# A1_0-_-1_0-_220V_12V.net
KiCad netlist of a schematic drawn in Altium Designer
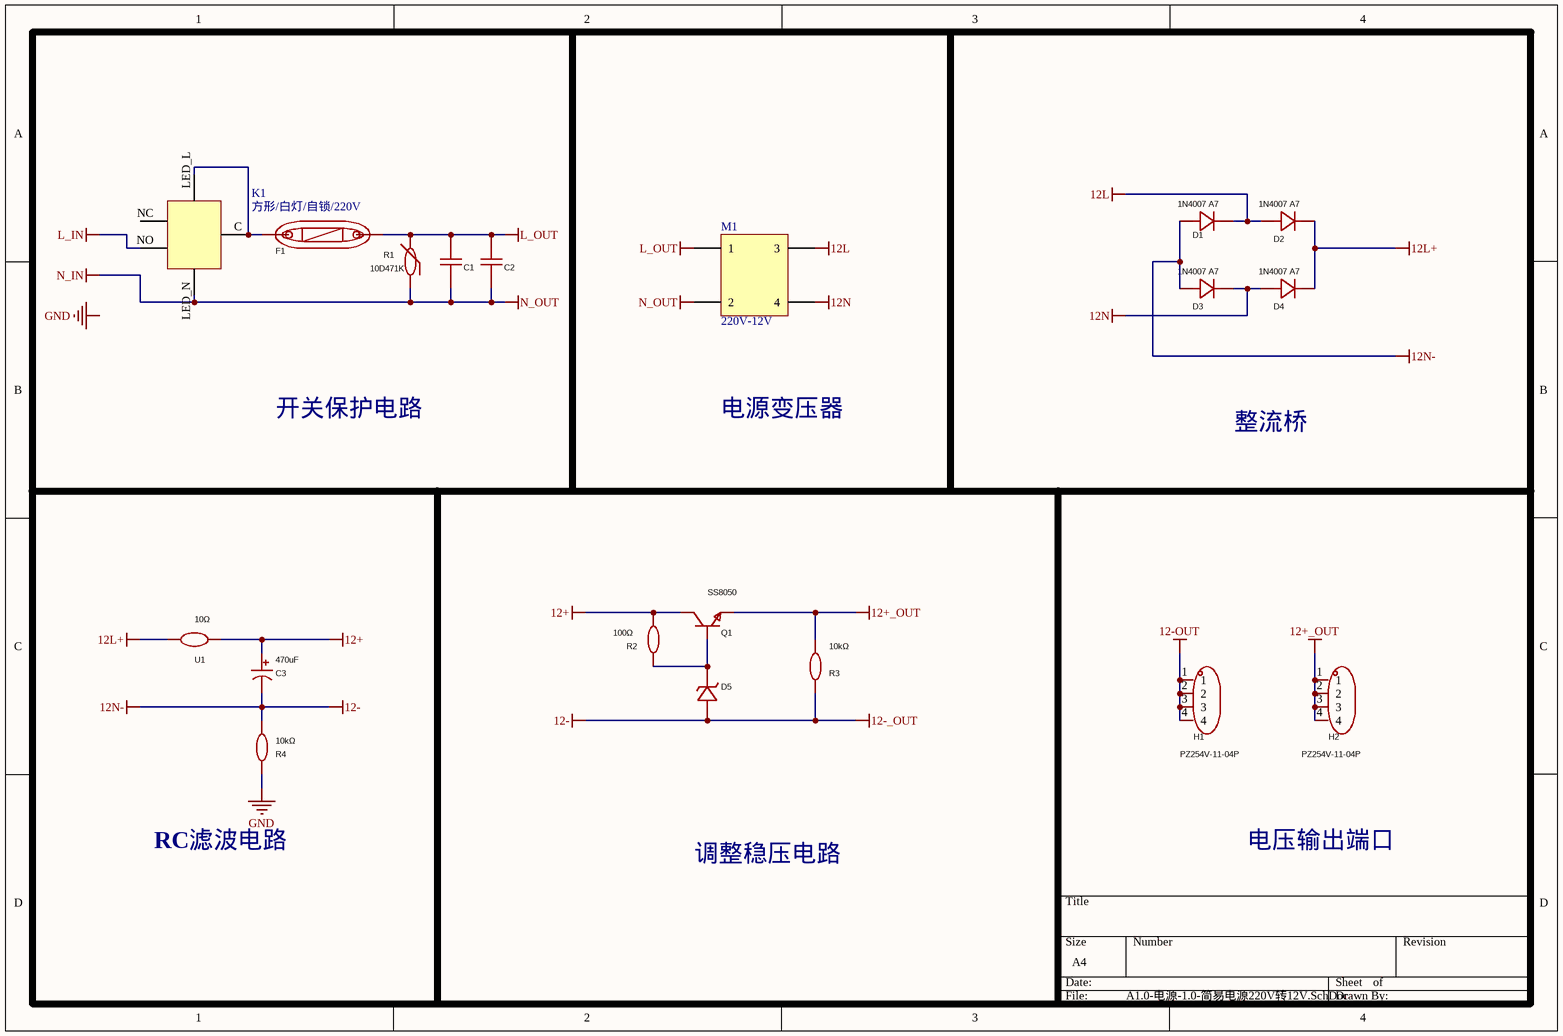
[diagram p0: A1.0-电源-1.0-简易电源220V转12V.SchDoc]

(export (version "E")
  (design (tool "Eeschema 10.0.6"))
  (components
    (comp (ref "C1")
      (value "470nF")
      (footprint "CAP-TH_L18.0-W8.5-P15.00-D0.8")
      (fields
        (field (name "MANUFACTURER") "KNSCHA(科尼盛)")
        (field (name "MANUFACTURER PART") "MPX474K31D4KN15800")
        (field (name "TOLERANCE") "±10%")
      )
      (libsource (lib "保护器件") (part "MPX474K31D4KN15800"))
    )
    (comp (ref "C2")
      (value "100nF")
      (footprint "CAP-TH_L18.0-W6.0-P15.00-D0.8")
      (fields
        (field (name "MANUFACTURER") "KNSCHA(科尼盛)")
        (field (name "MANUFACTURER PART") "MPX104K31D2KN15800")
        (field (name "TOLERANCE") "±10%")
      )
      (libsource (lib "保护器件") (part "MPX104K31D2KN15800"))
    )
    (comp (ref "C3")
      (value "470uF")
      (footprint "CAP-SMD_BD10.0-L10.3-W10.3-LS11.0-R-RD")
      (fields
        (field (name "MANUFACTURER") "ROQANG(容强)")
        (field (name "MANUFACTURER PART") "RVT1V471M1010")
        (field (name "TOLERANCE") "±20%")
      )
      (libsource (lib "电容") (part "RVT1V471M1010_C72519"))
    )
    (comp (ref "D1")
      (value "1N4007 A7")
      (footprint "SOD-123FL_L2.8-W1.8-LS3.7-RD")
      (fields (field (name "MANUFACTURER") "MSKSEMI(美森科)"))
      (libsource (lib "二极管") (part "1N4007 A7"))
    )
    (comp (ref "D2")
      (value "1N4007 A7")
      (footprint "SOD-123FL_L2.8-W1.8-LS3.7-RD")
      (fields (field (name "MANUFACTURER") "MSKSEMI(美森科)"))
      (libsource (lib "二极管") (part "1N4007 A7"))
    )
    (comp (ref "D3")
      (value "1N4007 A7")
      (footprint "SOD-123FL_L2.8-W1.8-LS3.7-RD")
      (fields (field (name "MANUFACTURER") "MSKSEMI(美森科)"))
      (libsource (lib "二极管") (part "1N4007 A7"))
    )
    (comp (ref "D4")
      (value "1N4007 A7")
      (footprint "SOD-123FL_L2.8-W1.8-LS3.7-RD")
      (fields (field (name "MANUFACTURER") "MSKSEMI(美森科)"))
      (libsource (lib "二极管") (part "1N4007 A7"))
    )
    (comp (ref "D5")
      (value "1SMAF4742A-MS")
      (footprint "SMAF_L3.5-W2.6-LS4.7-RD")
      (fields (field (name "MANUFACTURER") "MSKSEMI(美森科)"))
      (libsource (lib "二极管") (part "1SMAF4742A-MS"))
    )
    (comp (ref "F1")
      (value "保险丝透明座")
      (footprint "FUSE-TH_L24.5-W9.8-P22.5")
      (fields (field (name "MANUFACTURER") "xcfuse(旭程)"))
      (libsource (lib "保护器件") (part "保险丝透明座"))
    )
    (comp (ref "H1")
      (value "PZ254V-11-04P")
      (footprint "HDR-TH_4P-P2.54-V-M")
      (fields (field (name "MANUFACTURER") "XFCN(兴飞)"))
      (libsource (lib "连接器") (part "PZ254V-11-04P"))
    )
    (comp (ref "H2")
      (value "PZ254V-11-04P")
      (footprint "HDR-TH_4P-P2.54-V-M")
      (fields (field (name "MANUFACTURER") "XFCN(兴飞)"))
      (libsource (lib "连接器") (part "PZ254V-11-04P"))
    )
    (comp (ref "K1")
      (value "方形/白灯/自锁/220V")
      (footprint "方形/白灯/自锁/220V")
      (libsource (lib "开关") (part "方形/白灯/自锁/220V"))
    )
    (comp (ref "M1")
      (value "220V-12V")
      (footprint "220v-12v")
      (libsource (lib "电源器件") (part "220v转12v电源变压器"))
    )
    (comp (ref "Q1")
      (value "SS8050")
      (footprint "SOT-23-3_L2.9-W1.3-P1.90-LS2.4-BR")
      (fields (field (name "MANUFACTURER") "CJ(江苏长电/长晶)"))
      (libsource (lib "三极管") (part "SS8050_C2150"))
    )
    (comp (ref "R1")
      (value "10D471K")
      (footprint "RES-TH_L12.5-W6.7-P7.50-D1.2")
      (fields (field (name "MANUFACTURER") "RUILON(瑞隆源)"))
      (libsource (lib "保护器件") (part "10D471K_C8760"))
    )
    (comp (ref "R2")
      (value "100Ω")
      (footprint "R0805")
      (fields
        (field (name "MANUFACTURER") "UNI-ROYAL(厚声)")
        (field (name "MANUFACTURER PART") "0805W8F1000T5E")
        (field (name "TOLERANCE") "±1%")
      )
      (libsource (lib "电阻") (part "0805W8F1000T5E"))
    )
    (comp (ref "R3")
      (value "10kΩ")
      (footprint "R0805")
      (fields
        (field (name "MANUFACTURER") "UNI-ROYAL(厚声)")
        (field (name "MANUFACTURER PART") "0805W8J0103T5E")
        (field (name "TOLERANCE") "±5%")
      )
      (libsource (lib "电阻") (part "0805W8J0103T5E"))
    )
    (comp (ref "R4")
      (value "10kΩ")
      (footprint "R0805")
      (fields
        (field (name "MANUFACTURER") "UNI-ROYAL(厚声)")
        (field (name "MANUFACTURER PART") "0805W8J0103T5E")
        (field (name "TOLERANCE") "±5%")
      )
      (libsource (lib "电阻") (part "0805W8J0103T5E"))
    )
    (comp (ref "U1")
      (value "10Ω")
      (footprint "RES-TH_L22.0-W10.0-P26.00-D1.0")
      (fields
        (field (name "MANUFACTURER") "VO(翔胜)")
        (field (name "MANUFACTURER PART") "SQP5W-10Ω±5%-9P")
        (field (name "TOLERANCE") "±5%")
      )
      (libsource (lib "电阻") (part "SQP5W-10Ω±5%-9P"))
    )
  )
  (nets
    (net (code "1") (name "12+") (class "Default")
      (node (ref "C3") (pin "1") (pinfunction "1_1") (pintype "passive"))
      (node (ref "Q1") (pin "3") (pinfunction "C_3") (pintype "passive"))
      (node (ref "R2") (pin "2") (pinfunction "2_2") (pintype "passive"))
      (node (ref "U1") (pin "2") (pinfunction "2_2") (pintype "passive"))
    )
    (net (code "2") (name "12+_OUT") (class "Default")
      (node (ref "H2") (pin "1") (pinfunction "1_1") (pintype "passive"))
      (node (ref "H2") (pin "2") (pinfunction "2_2") (pintype "passive"))
      (node (ref "H2") (pin "3") (pinfunction "3_3") (pintype "passive"))
      (node (ref "H2") (pin "4") (pinfunction "4_4") (pintype "passive"))
      (node (ref "Q1") (pin "2") (pinfunction "E_2") (pintype "passive"))
      (node (ref "R3") (pin "1") (pinfunction "1_1") (pintype "passive"))
    )
    (net (code "3") (name "12-") (class "Default")
      (node (ref "C3") (pin "2") (pinfunction "2_2") (pintype "passive"))
      (node (ref "D1") (pin "2") (pinfunction "A_2") (pintype "passive"))
      (node (ref "D3") (pin "2") (pinfunction "A_2") (pintype "passive"))
      (node (ref "D5") (pin "2") (pinfunction "A_2") (pintype "passive"))
      (node (ref "R3") (pin "2") (pinfunction "2_2") (pintype "passive"))
      (node (ref "R4") (pin "2") (pinfunction "2_2") (pintype "passive"))
    )
    (net (code "4") (name "12-OUT") (class "Default")
      (node (ref "H1") (pin "1") (pinfunction "1_1") (pintype "passive"))
      (node (ref "H1") (pin "2") (pinfunction "2_2") (pintype "passive"))
      (node (ref "H1") (pin "3") (pinfunction "3_3") (pintype "passive"))
      (node (ref "H1") (pin "4") (pinfunction "4_4") (pintype "passive"))
    )
    (net (code "5") (name "12L") (class "Default")
      (node (ref "D1") (pin "1") (pinfunction "K_1") (pintype "passive"))
      (node (ref "D2") (pin "2") (pinfunction "A_2") (pintype "passive"))
      (node (ref "M1") (pin "3") (pinfunction "3_3") (pintype "passive"))
    )
    (net (code "6") (name "12L+") (class "Default")
      (node (ref "D2") (pin "1") (pinfunction "K_1") (pintype "passive"))
      (node (ref "D4") (pin "1") (pinfunction "K_1") (pintype "passive"))
      (node (ref "U1") (pin "1") (pinfunction "1_1") (pintype "passive"))
    )
    (net (code "7") (name "12N") (class "Default")
      (node (ref "D3") (pin "1") (pinfunction "K_1") (pintype "passive"))
      (node (ref "D4") (pin "2") (pinfunction "A_2") (pintype "passive"))
      (node (ref "M1") (pin "4") (pinfunction "4_4") (pintype "passive"))
    )
    (net (code "8") (name "GND") (class "Default")
      (node (ref "R4") (pin "1") (pinfunction "1_1") (pintype "passive"))
    )
    (net (code "9") (name "L_IN") (class "Default")
      (node (ref "K1") (pin "NO") (pinfunction "2_NO") (pintype "passive"))
    )
    (net (code "10") (name "L_OUT") (class "Default")
      (node (ref "C1") (pin "2") (pinfunction "2_2") (pintype "passive"))
      (node (ref "C2") (pin "2") (pinfunction "2_2") (pintype "passive"))
      (node (ref "F1") (pin "2") (pinfunction "2_2") (pintype "passive"))
      (node (ref "M1") (pin "1") (pinfunction "1_1") (pintype "passive"))
      (node (ref "R1") (pin "2") (pinfunction "2_2") (pintype "passive"))
    )
    (net (code "11") (name "N_IN") (class "Default")
      (node (ref "C1") (pin "1") (pinfunction "1_1") (pintype "passive"))
      (node (ref "C2") (pin "1") (pinfunction "1_1") (pintype "passive"))
      (node (ref "K1") (pin "LED_N") (pinfunction "5_LED_N") (pintype "passive"))
      (node (ref "M1") (pin "2") (pinfunction "2_2") (pintype "passive"))
      (node (ref "R1") (pin "1") (pinfunction "1_1") (pintype "passive"))
    )
    (net (code "12") (name "Net-(D5-K)") (class "Default")
      (node (ref "D5") (pin "1") (pinfunction "K_1") (pintype "passive"))
      (node (ref "Q1") (pin "1") (pinfunction "B_1") (pintype "passive"))
      (node (ref "R2") (pin "1") (pinfunction "1_1") (pintype "passive"))
    )
    (net (code "13") (name "Net-(K1-3)") (class "Default")
      (node (ref "F1") (pin "1") (pinfunction "1_1") (pintype "passive"))
      (node (ref "K1") (pin "C") (pinfunction "3_C") (pintype "passive"))
      (node (ref "K1") (pin "LED_L") (pinfunction "4_LED_L") (pintype "passive"))
    )
    (net (code "14") (name "unconnected-(K1-1-PadNC)") (class "Default")
      (node (ref "K1") (pin "NC") (pinfunction "1_NC") (pintype "passive"))
    )
  )
)
